# board_TP4056.net
KiCad netlist of a schematic drawn in EAGLE
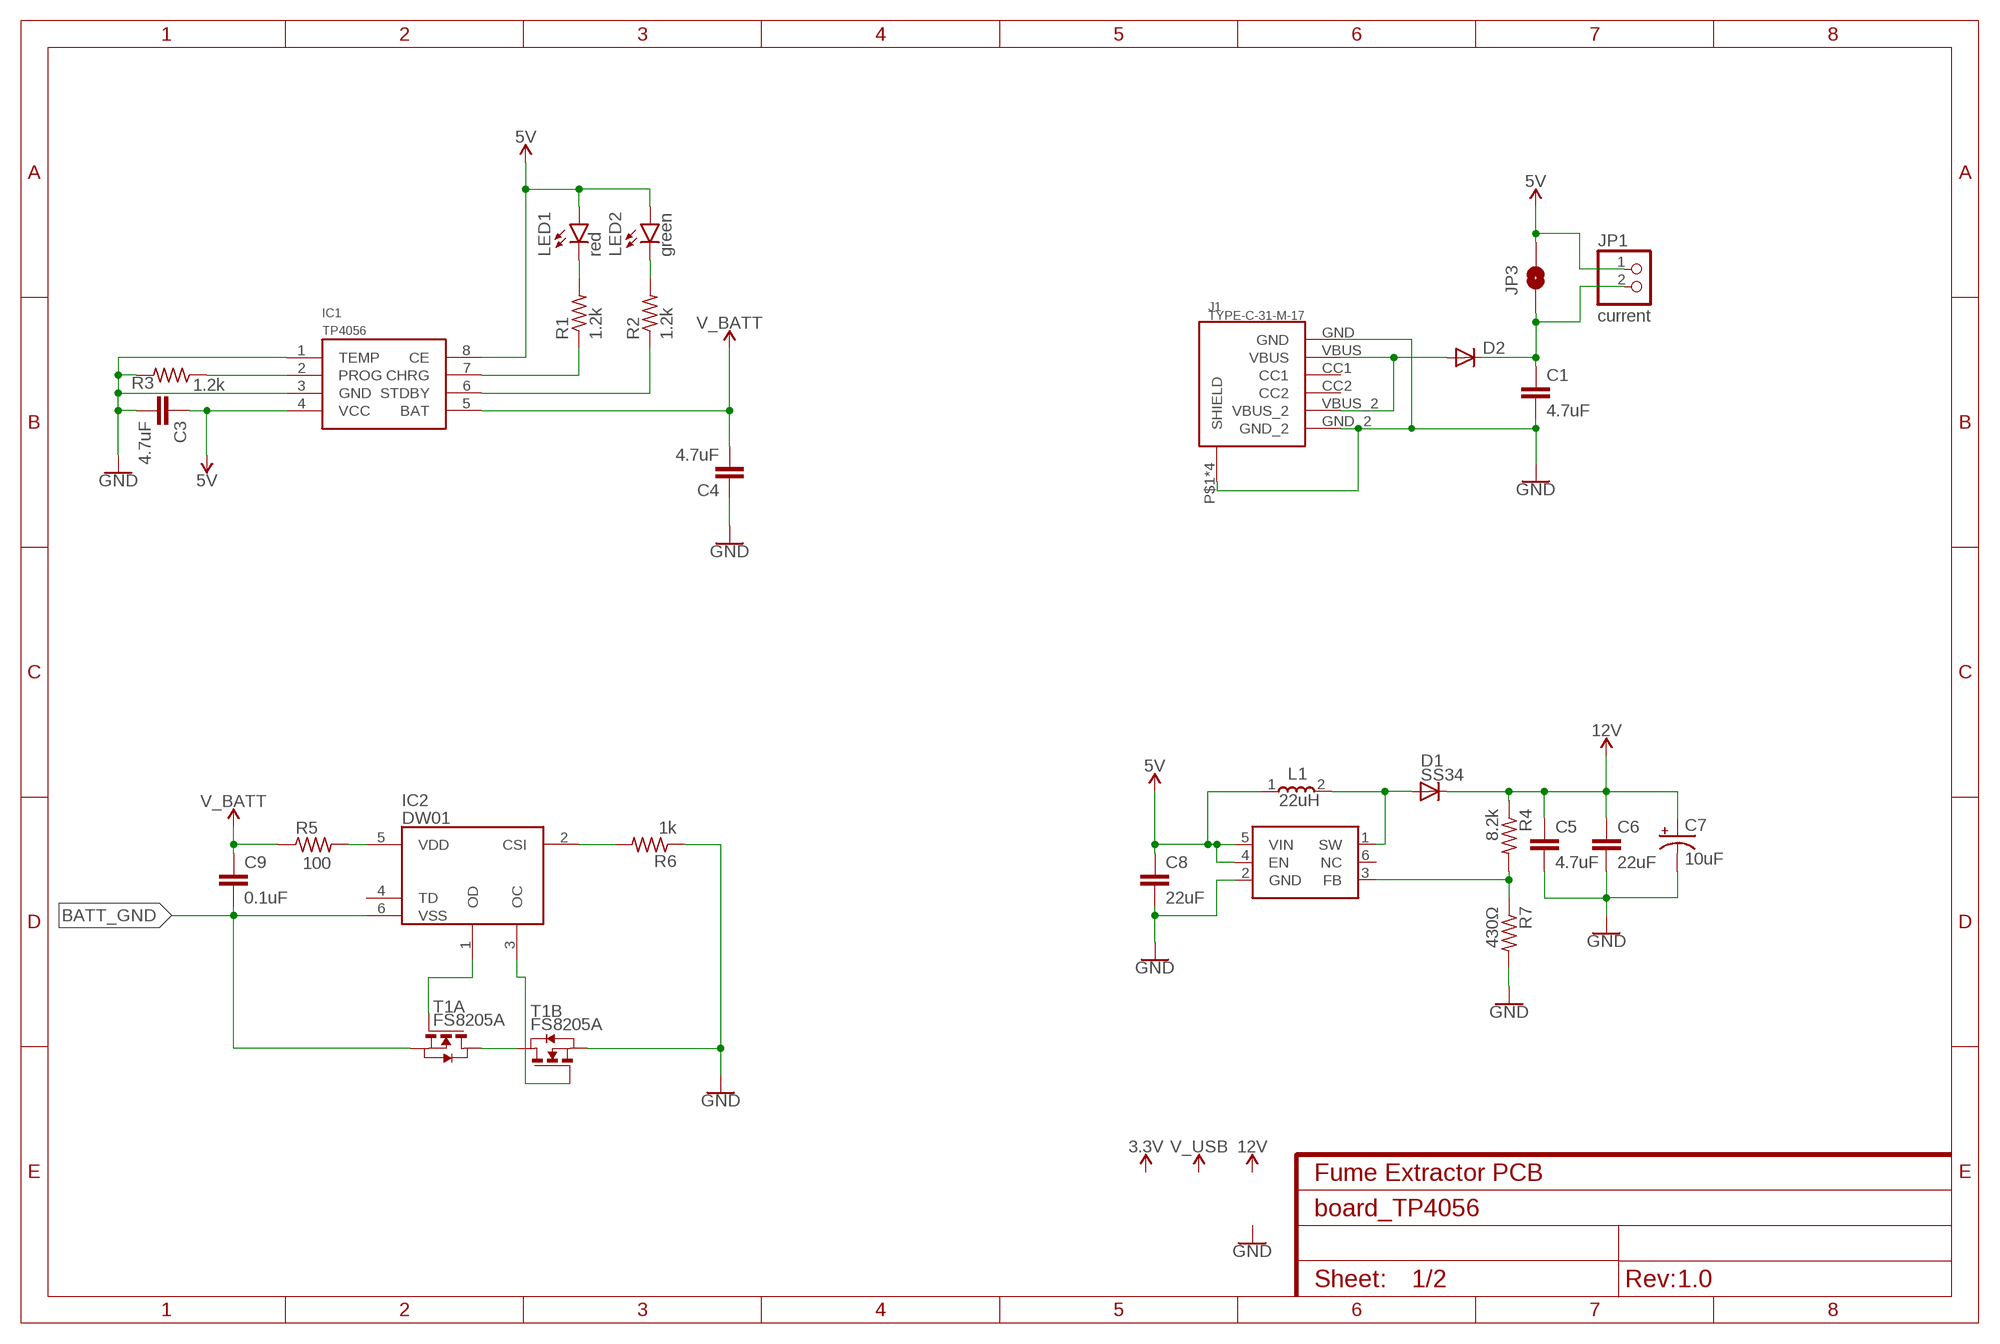
[diagram p0: schematic, sheet 1]
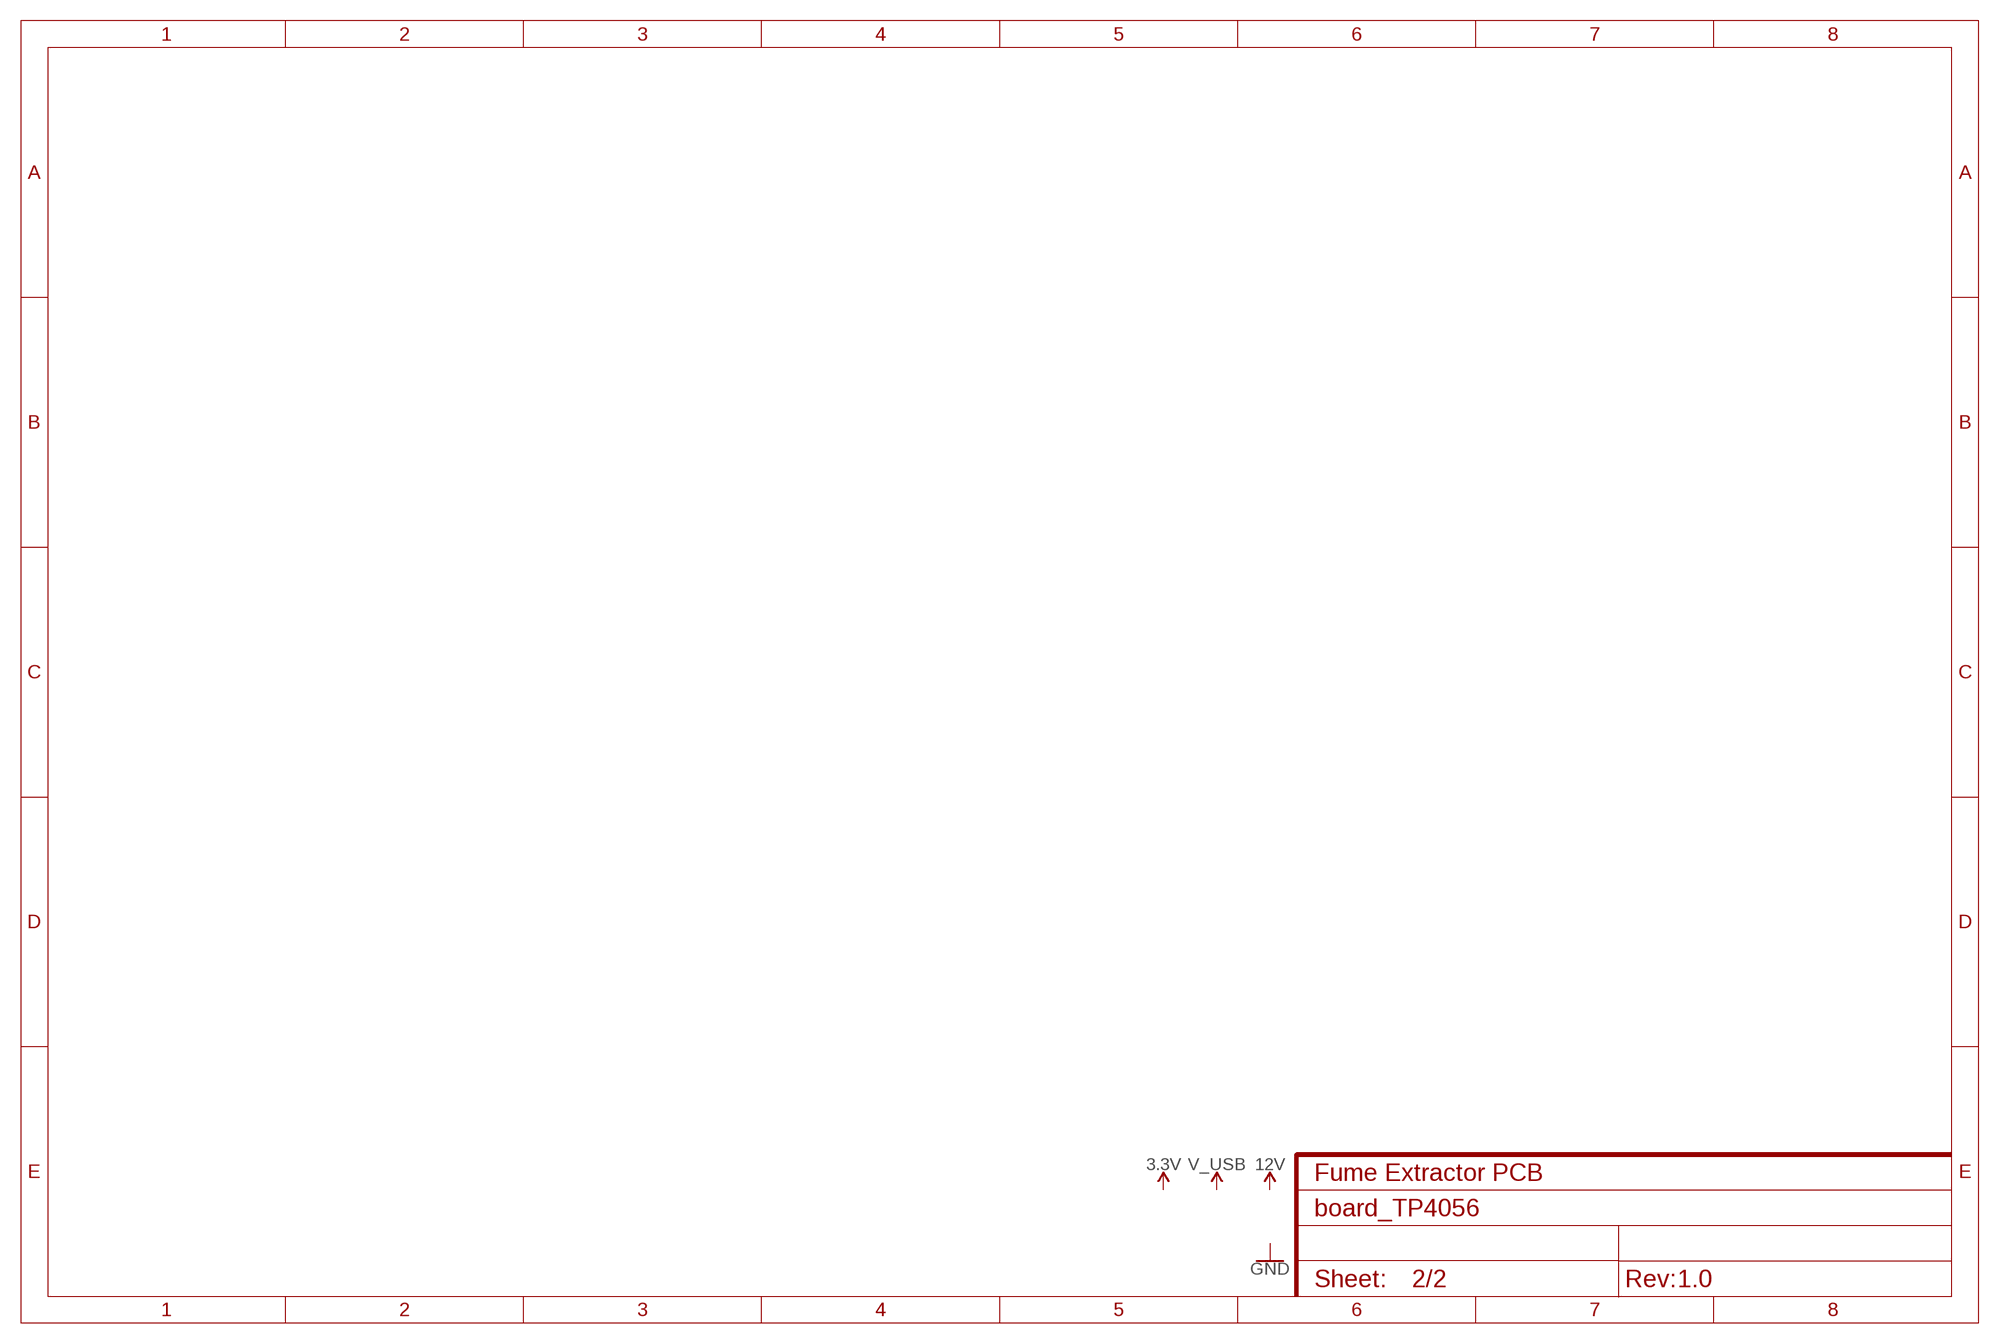
[diagram p1: schematic, sheet 2]

(export (version "E")
  (design (tool "Eeschema 10.0.6"))
  (components
    (comp (ref "C1")
      (value "4.7uF")
      (footprint "eagle-import:C0805")
      (libsource (lib "eagle-import") (part "C-EUC0805"))
    )
    (comp (ref "C3")
      (value "4.7uF")
      (footprint "eagle-import:C0805")
      (libsource (lib "eagle-import") (part "C-EUC0805"))
    )
    (comp (ref "C4")
      (value "4.7uF")
      (footprint "eagle-import:C0805")
      (libsource (lib "eagle-import") (part "C-EUC0805"))
    )
    (comp (ref "C5")
      (value "4.7uF")
      (footprint "eagle-import:C0805")
      (libsource (lib "eagle-import") (part "C-EUC0805"))
    )
    (comp (ref "C6")
      (value "22uF")
      (footprint "eagle-import:C0805")
      (libsource (lib "eagle-import") (part "C-EUC0805"))
    )
    (comp (ref "C7")
      (value "10uF")
      (footprint "eagle-import:SMC_A")
      (libsource (lib "eagle-import") (part "CPOL-USSMCA"))
    )
    (comp (ref "C8")
      (value "22uF")
      (footprint "eagle-import:C0805")
      (libsource (lib "eagle-import") (part "C-EUC0805"))
    )
    (comp (ref "C9")
      (value "0.1uF")
      (footprint "eagle-import:C0805")
      (libsource (lib "eagle-import") (part "C-EUC0805"))
    )
    (comp (ref "D1")
      (value "SS34")
      (footprint "eagle-import:DO214AC")
      (libsource (lib "eagle-import") (part "DIODE-DO214AC"))
    )
    (comp (ref "D2")
      (value "DIODE-SOD-123")
      (footprint "eagle-import:SOD-123")
      (libsource (lib "eagle-import") (part "DIODE-SOD-123"))
    )
    (comp (ref "IC1")
      (value "TP4056")
      (footprint "eagle-import:SOP-8")
      (libsource (lib "eagle-import") (part "TP4056"))
    )
    (comp (ref "IC2")
      (value "DW01")
      (footprint "eagle-import:SOT95P280X135-6N")
      (libsource (lib "eagle-import") (part "DW01"))
    )
    (comp (ref "J1")
      (value "TYPE-C-31-M-17")
      (footprint "eagle-import:TYPE-C-31-M-17")
      (libsource (lib "eagle-import") (part "TYPE-C-31-M-17"))
    )
    (comp (ref "JP1")
      (value "current")
      (footprint "eagle-import:1X02_OCT")
      (libsource (lib "eagle-import") (part "PINHD-1X2/OCT"))
    )
    (comp (ref "JP3")
      (value "JUMPER-SMT_2_NO_NO-SILK")
      (footprint "eagle-import:SMT-JUMPER_2_NO_NO-SILK")
      (libsource (lib "eagle-import") (part "JUMPER-SMT_2_NO_NO-SILK"))
    )
    (comp (ref "L1")
      (value "22uH")
      (footprint "eagle-import:INDPM7066X300N")
      (fields (field (name "MANUFACTURER_PART_NUMBER") "BCIHP0730-220M"))
      (libsource (lib "eagle-import") (part "BCIHP0730-220M"))
    )
    (comp (ref "LED1")
      (value "red")
      (footprint "eagle-import:CHIP-LED0805")
      (libsource (lib "eagle-import") (part "LEDCHIP-LED0805"))
    )
    (comp (ref "LED2")
      (value "green")
      (footprint "eagle-import:CHIP-LED0805")
      (libsource (lib "eagle-import") (part "LEDCHIP-LED0805"))
    )
    (comp (ref "R1")
      (value "1.2k")
      (footprint "eagle-import:R0805")
      (libsource (lib "eagle-import") (part "R-US_R0805"))
    )
    (comp (ref "R2")
      (value "1.2k")
      (footprint "eagle-import:R0805")
      (libsource (lib "eagle-import") (part "R-US_R0805"))
    )
    (comp (ref "R3")
      (value "1.2k")
      (footprint "eagle-import:R0805")
      (libsource (lib "eagle-import") (part "R-US_R0805"))
    )
    (comp (ref "R4")
      (value "8.2k")
      (footprint "eagle-import:R0805")
      (libsource (lib "eagle-import") (part "R-US_R0805"))
    )
    (comp (ref "R5")
      (value "100")
      (footprint "eagle-import:R0805")
      (libsource (lib "eagle-import") (part "R-US_R0805"))
    )
    (comp (ref "R6")
      (value "1k")
      (footprint "eagle-import:R0805")
      (libsource (lib "eagle-import") (part "R-US_R0805"))
    )
    (comp (ref "R7")
      (value "430Ω")
      (footprint "eagle-import:R0805")
      (libsource (lib "eagle-import") (part "R-US_R0805"))
    )
    (comp (ref "T1")
      (value "FS8205A")
      (footprint "eagle-import:TSSOP-8")
      (libsource (lib "eagle-import") (part "FS8205A-MOSFET"))
    )
    (comp (ref "U1")
      (value "MT3608")
      (footprint "eagle-import:SOT23-6")
      (libsource (lib "eagle-import") (part "MT3608"))
    )
  )
  (nets
    (net (code "2") (name "5V") (class "Default")
      (node (ref "C3") (pin "1") (pinfunction "1_1") (pintype "passive"))
      (node (ref "C8") (pin "1") (pinfunction "1_1") (pintype "passive"))
      (node (ref "IC1") (pin "4") (pinfunction "VCC_4") (pintype "bidirectional"))
      (node (ref "IC1") (pin "8") (pinfunction "CE_8") (pintype "bidirectional"))
      (node (ref "JP1") (pin "1") (pinfunction "1_1") (pintype "passive"))
      (node (ref "JP3") (pin "2") (pinfunction "2_2") (pintype "passive"))
      (node (ref "L1") (pin "1") (pinfunction "1_1") (pintype "bidirectional"))
      (node (ref "LED1") (pin "A") (pinfunction "A_A") (pintype "passive"))
      (node (ref "LED2") (pin "A") (pinfunction "A_A") (pintype "passive"))
      (node (ref "U1") (pin "4") (pinfunction "EN_4") (pintype "bidirectional"))
      (node (ref "U1") (pin "5") (pinfunction "VIN_5") (pintype "bidirectional"))
    )
    (net (code "3") (name "12V") (class "Default")
      (node (ref "C5") (pin "1") (pinfunction "1_1") (pintype "passive"))
      (node (ref "C6") (pin "1") (pinfunction "1_1") (pintype "passive"))
      (node (ref "C7") (pin "+") (pinfunction "+_+") (pintype "passive"))
      (node (ref "D1") (pin "C") (pinfunction "C_C") (pintype "passive"))
      (node (ref "R4") (pin "1") (pinfunction "1_1") (pintype "passive"))
    )
    (net (code "4") (name "BATT_GND") (class "Default")
      (node (ref "C9") (pin "2") (pinfunction "2_2") (pintype "passive"))
      (node (ref "IC2") (pin "6") (pinfunction "VSS_6") (pintype "bidirectional"))
      (node (ref "T1") (pin "2") (pinfunction "S_2") (pintype "passive"))
      (node (ref "T1") (pin "3") (pinfunction "S_3") (pintype "passive"))
    )
    (net (code "5") (name "GND") (class "Default")
      (node (ref "C1") (pin "2") (pinfunction "2_2") (pintype "passive"))
      (node (ref "C3") (pin "2") (pinfunction "2_2") (pintype "passive"))
      (node (ref "C4") (pin "1") (pinfunction "1_1") (pintype "passive"))
      (node (ref "C5") (pin "2") (pinfunction "2_2") (pintype "passive"))
      (node (ref "C6") (pin "2") (pinfunction "2_2") (pintype "passive"))
      (node (ref "C7") (pin "-") (pinfunction "-_-") (pintype "passive"))
      (node (ref "C8") (pin "2") (pinfunction "2_2") (pintype "passive"))
      (node (ref "IC1") (pin "1") (pinfunction "TEMP_1") (pintype "bidirectional"))
      (node (ref "IC1") (pin "3") (pinfunction "GND_3") (pintype "bidirectional"))
      (node (ref "J1") (pin "GND") (pinfunction "GND_GND") (pintype "bidirectional"))
      (node (ref "J1") (pin "GND_2") (pinfunction "GND_2_GND_2") (pintype "bidirectional"))
      (node (ref "J1") (pin "P$1") (pinfunction "SHIELD_P$1") (pintype "bidirectional"))
      (node (ref "J1") (pin "P$2") (pinfunction "SHIELD_P$2") (pintype "bidirectional"))
      (node (ref "J1") (pin "P$3") (pinfunction "SHIELD_P$3") (pintype "bidirectional"))
      (node (ref "J1") (pin "P$4") (pinfunction "SHIELD_P$4") (pintype "bidirectional"))
      (node (ref "R3") (pin "2") (pinfunction "2_2") (pintype "passive"))
      (node (ref "R6") (pin "1") (pinfunction "1_1") (pintype "passive"))
      (node (ref "R7") (pin "2") (pinfunction "2_2") (pintype "passive"))
      (node (ref "T1") (pin "6") (pinfunction "S_6") (pintype "passive"))
      (node (ref "T1") (pin "7") (pinfunction "S_7") (pintype "passive"))
      (node (ref "U1") (pin "2") (pinfunction "GND_2") (pintype "bidirectional"))
    )
    (net (code "6") (name "Net-(C1-Pad1)") (class "Default")
      (node (ref "C1") (pin "1") (pinfunction "1_1") (pintype "passive"))
      (node (ref "D2") (pin "C") (pinfunction "C_C") (pintype "passive"))
      (node (ref "JP1") (pin "2") (pinfunction "2_2") (pintype "passive"))
      (node (ref "JP3") (pin "1") (pinfunction "1_1") (pintype "passive"))
    )
    (net (code "7") (name "Net-(D2-PadA)") (class "Default")
      (node (ref "D2") (pin "A") (pinfunction "A_A") (pintype "passive"))
      (node (ref "J1") (pin "VBUS") (pinfunction "VBUS_VBUS") (pintype "bidirectional"))
      (node (ref "J1") (pin "VBUS_2") (pinfunction "VBUS_2_VBUS_2") (pintype "bidirectional"))
    )
    (net (code "8") (name "Net-(IC1-CHRG)") (class "Default")
      (node (ref "IC1") (pin "7") (pinfunction "CHRG_7") (pintype "bidirectional"))
      (node (ref "R1") (pin "1") (pinfunction "1_1") (pintype "passive"))
    )
    (net (code "9") (name "Net-(IC1-PROG)") (class "Default")
      (node (ref "IC1") (pin "2") (pinfunction "PROG_2") (pintype "bidirectional"))
      (node (ref "R3") (pin "1") (pinfunction "1_1") (pintype "passive"))
    )
    (net (code "10") (name "Net-(IC1-STDBY)") (class "Default")
      (node (ref "IC1") (pin "6") (pinfunction "STDBY_6") (pintype "bidirectional"))
      (node (ref "R2") (pin "1") (pinfunction "1_1") (pintype "passive"))
    )
    (net (code "11") (name "Net-(IC2-CSI)") (class "Default")
      (node (ref "IC2") (pin "2") (pinfunction "CSI_2") (pintype "bidirectional"))
      (node (ref "R6") (pin "2") (pinfunction "2_2") (pintype "passive"))
    )
    (net (code "12") (name "Net-(IC2-OC)") (class "Default")
      (node (ref "IC2") (pin "3") (pinfunction "OC_3") (pintype "bidirectional"))
      (node (ref "T1") (pin "5") (pinfunction "G_5") (pintype "passive"))
    )
    (net (code "13") (name "Net-(IC2-OD)") (class "Default")
      (node (ref "IC2") (pin "1") (pinfunction "OD_1") (pintype "bidirectional"))
      (node (ref "T1") (pin "4") (pinfunction "G_4") (pintype "passive"))
    )
    (net (code "14") (name "Net-(IC2-VDD)") (class "Default")
      (node (ref "IC2") (pin "5") (pinfunction "VDD_5") (pintype "bidirectional"))
      (node (ref "R5") (pin "2") (pinfunction "2_2") (pintype "passive"))
    )
    (net (code "15") (name "Net-(LED1-PadC)") (class "Default")
      (node (ref "LED1") (pin "C") (pinfunction "C_C") (pintype "passive"))
      (node (ref "R1") (pin "2") (pinfunction "2_2") (pintype "passive"))
    )
    (net (code "16") (name "Net-(LED2-PadC)") (class "Default")
      (node (ref "LED2") (pin "C") (pinfunction "C_C") (pintype "passive"))
      (node (ref "R2") (pin "2") (pinfunction "2_2") (pintype "passive"))
    )
    (net (code "17") (name "Net-(T1A-D)") (class "Default")
      (node (ref "T1") (pin "1") (pinfunction "D_1") (pintype "passive"))
      (node (ref "T1") (pin "8") (pinfunction "D_8") (pintype "passive"))
    )
    (net (code "18") (name "Net-(U1-FB)") (class "Default")
      (node (ref "R4") (pin "2") (pinfunction "2_2") (pintype "passive"))
      (node (ref "R7") (pin "1") (pinfunction "1_1") (pintype "passive"))
      (node (ref "U1") (pin "3") (pinfunction "FB_3") (pintype "bidirectional"))
    )
    (net (code "19") (name "Net-(U1-SW)") (class "Default")
      (node (ref "D1") (pin "A") (pinfunction "A_A") (pintype "passive"))
      (node (ref "L1") (pin "2") (pinfunction "2_2") (pintype "bidirectional"))
      (node (ref "U1") (pin "1") (pinfunction "SW_1") (pintype "bidirectional"))
    )
    (net (code "20") (name "V_BATT") (class "Default")
      (node (ref "C4") (pin "2") (pinfunction "2_2") (pintype "passive"))
      (node (ref "C9") (pin "1") (pinfunction "1_1") (pintype "passive"))
      (node (ref "IC1") (pin "5") (pinfunction "BAT_5") (pintype "bidirectional"))
      (node (ref "R5") (pin "1") (pinfunction "1_1") (pintype "passive"))
    )
    (net (code "22") (name "unconnected-(IC2-TD-Pad4)") (class "Default")
      (node (ref "IC2") (pin "4") (pinfunction "TD_4") (pintype "bidirectional"))
    )
    (net (code "23") (name "unconnected-(J1-PadCC1)") (class "Default")
      (node (ref "J1") (pin "CC1") (pinfunction "CC1_CC1") (pintype "bidirectional"))
    )
    (net (code "24") (name "unconnected-(J1-PadCC2)") (class "Default")
      (node (ref "J1") (pin "CC2") (pinfunction "CC2_CC2") (pintype "bidirectional"))
    )
    (net (code "25") (name "unconnected-(U1-NC-Pad6)") (class "Default")
      (node (ref "U1") (pin "6") (pinfunction "NC_6") (pintype "bidirectional"))
    )
  )
)
